# Receiver.net
KiCad netlist of a schematic drawn in Altium Designer
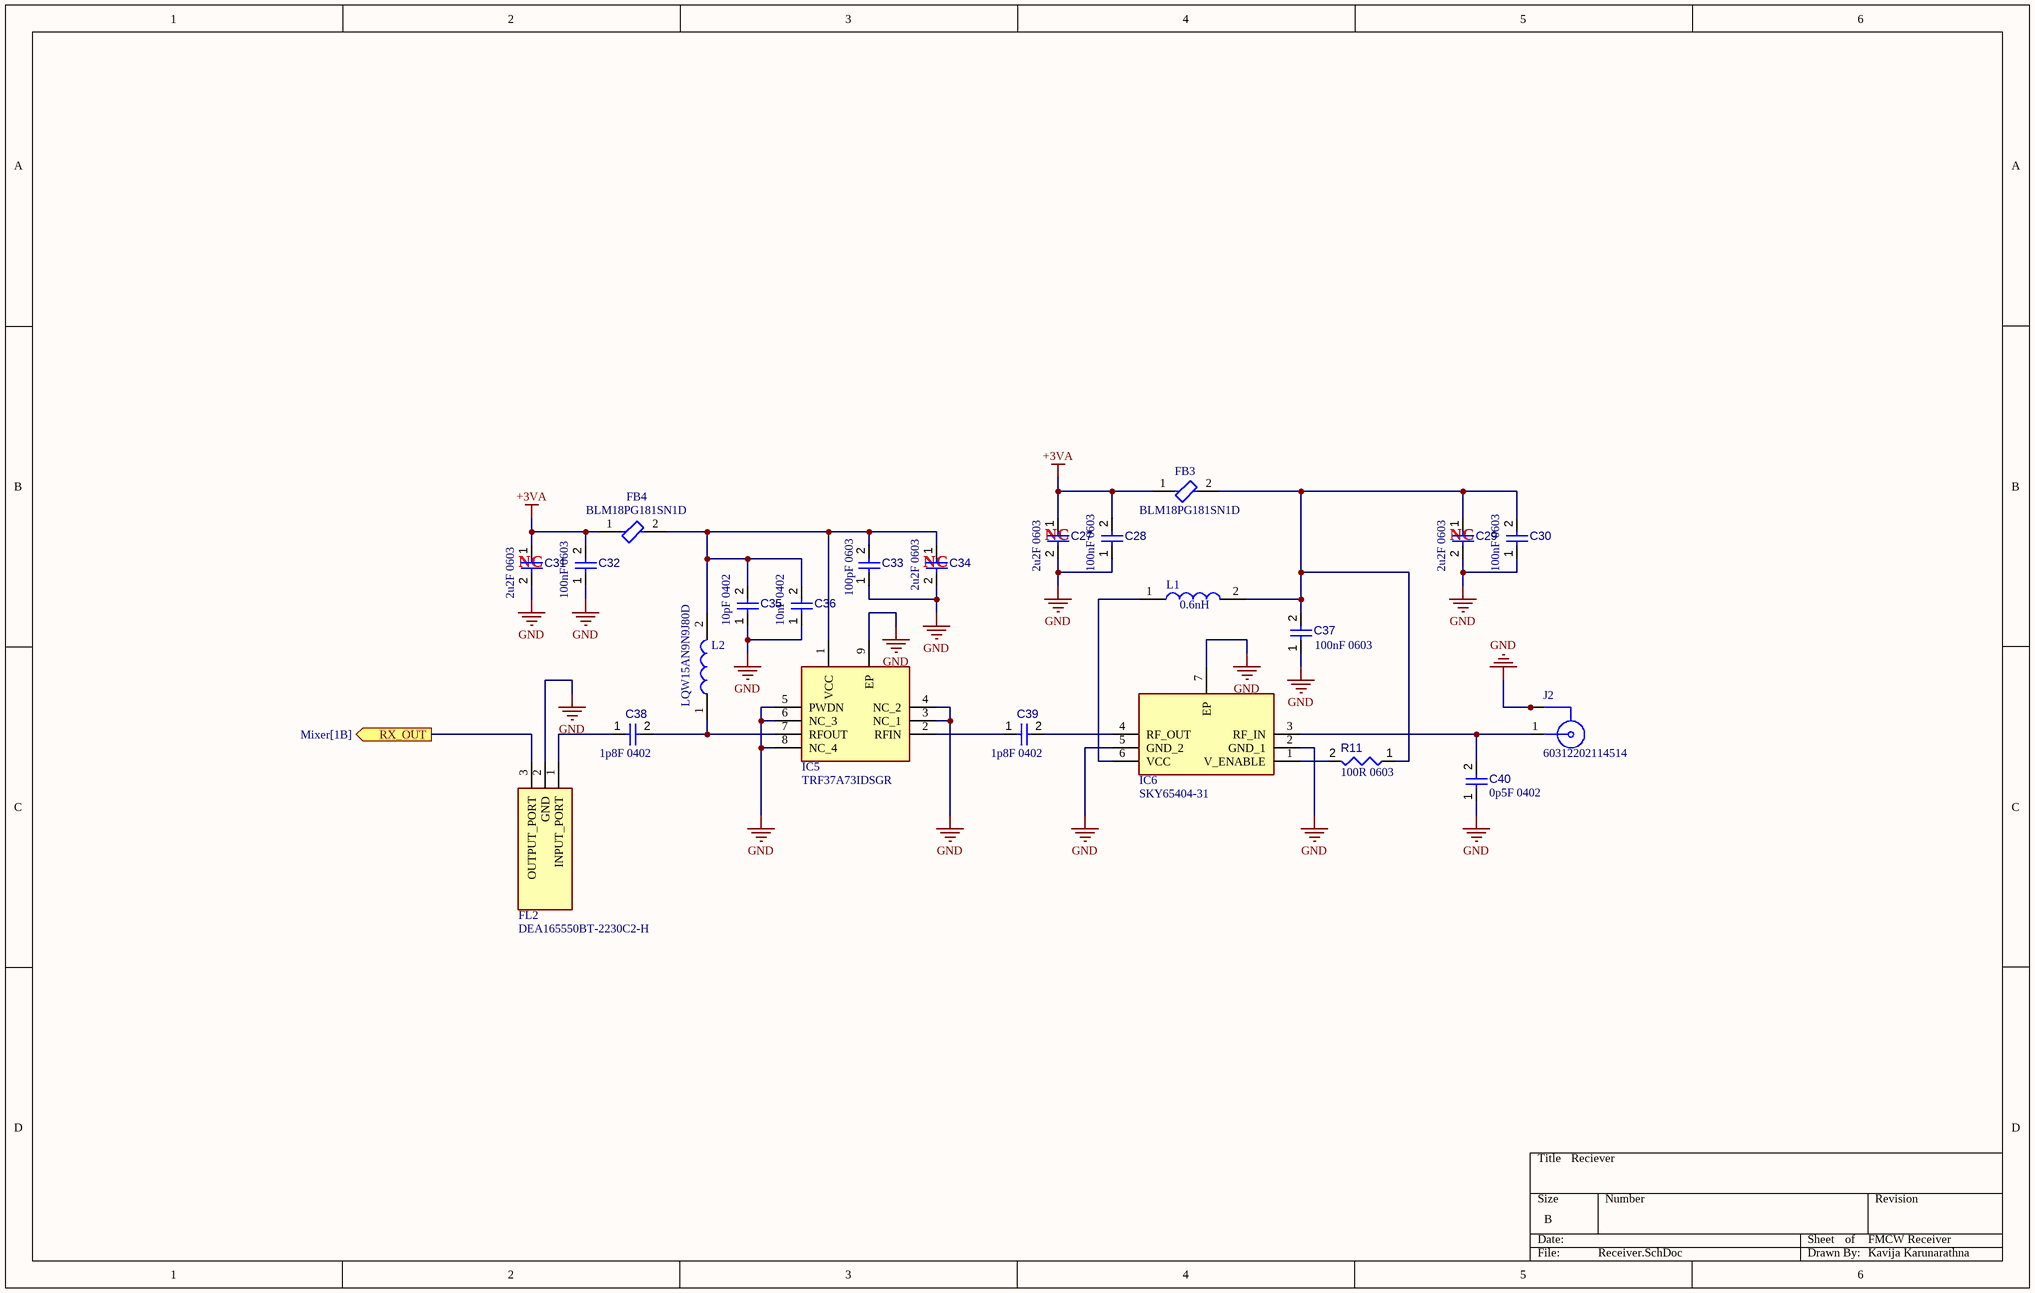
[diagram p0: Receiver.SchDoc]

(export (version "E")
  (design (tool "Eeschema 10.0.6"))
  (components
    (comp (ref "C27")
      (value "2u2F 0603")
      (footprint "CAPC0603(1608)100_L")
      (description "Multilayer Ceramic Capacitors MLCC - SMD/SMT 0603 10nF 16volts X7R 10%")
      (fields (field (name "TOLERANCE") "20%") (field (name "MANUFACTURER PART NO") "VJ0603G225KXQCW1BC"))
      (libsource (lib "Kavija Karunarathna") (part "CAP-NP-2"))
    )
    (comp (ref "C28")
      (value "100nF 0603")
      (footprint "CAPC0603(1608)100_L")
      (description "Chip Capacitor, 1µF +/-0.1%, 25V, 0603, Thickness 1 mm")
      (fields (field (name "TOLERANCE") "20%") (field (name "MANUFACTURER PART NO") "0603X104K250CT"))
      (libsource (lib "Kavija Karunarathna") (part "CAP-NP-2"))
    )
    (comp (ref "C29")
      (value "2u2F 0603")
      (footprint "CAPC0603(1608)100_L")
      (description "Multilayer Ceramic Capacitors MLCC - SMD/SMT 0603 10nF 16volts X7R 10%")
      (fields (field (name "TOLERANCE") "20%") (field (name "MANUFACTURER PART NO") "VJ0603G225KXQCW1BC"))
      (libsource (lib "Kavija Karunarathna") (part "CAP-NP-2"))
    )
    (comp (ref "C30")
      (value "100nF 0603")
      (footprint "CAPC0603(1608)100_L")
      (description "Chip Capacitor, 1µF +/-0.1%, 25V, 0603, Thickness 1 mm")
      (fields (field (name "TOLERANCE") "20%") (field (name "MANUFACTURER PART NO") "0603X104K250CT"))
      (libsource (lib "Kavija Karunarathna") (part "CAP-NP-2"))
    )
    (comp (ref "C31")
      (value "2u2F 0603")
      (footprint "CAPC0603(1608)100_L")
      (description "Multilayer Ceramic Capacitors MLCC - SMD/SMT 0603 10nF 16volts X7R 10%")
      (fields (field (name "TOLERANCE") "20%") (field (name "MANUFACTURER PART NO") "VJ0603G225KXQCW1BC"))
      (libsource (lib "Kavija Karunarathna") (part "CAP-NP-2"))
    )
    (comp (ref "C32")
      (value "100nF 0603")
      (footprint "CAPC0603(1608)100_L")
      (description "Chip Capacitor, 1µF +/-0.1%, 25V, 0603, Thickness 1 mm")
      (fields (field (name "TOLERANCE") "20%") (field (name "MANUFACTURER PART NO") "0603X104K250CT"))
      (libsource (lib "Kavija Karunarathna") (part "CAP-NP-2"))
    )
    (comp (ref "C33")
      (value "100pF 0603")
      (footprint "CAPC0603(1608)100_L")
      (description "Chip Capacitor, 1µF +/-0.1%, 25V, 0603, Thickness 1 mm")
      (fields (field (name "TOLERANCE") "20%") (field (name "MANUFACTURER PART NO") "06033A101GAT2A"))
      (libsource (lib "Kavija Karunarathna") (part "CAP-NP-2"))
    )
    (comp (ref "C34")
      (value "2u2F 0603")
      (footprint "CAPC0603(1608)100_L")
      (description "Multilayer Ceramic Capacitors MLCC - SMD/SMT 0603 10nF 16volts X7R 10%")
      (fields (field (name "TOLERANCE") "20%") (field (name "MANUFACTURER PART NO") "VJ0603G225KXQCW1BC"))
      (libsource (lib "Kavija Karunarathna") (part "CAP-NP-2"))
    )
    (comp (ref "C35")
      (value "10pF 0402")
      (footprint "CAPC0402(1005)60_L")
      (description "Multilayer Ceramic Capacitors MLCC - SMD/SMT 50 V 10 pF C0G 0402 1%")
      (fields (field (name "TOLERANCE") "20%") (field (name "MANUFACTURER PART NO") "CQ0402FRNPO9BN100"))
      (libsource (lib "Kavija Karunarathna") (part "CAP-NP-2"))
    )
    (comp (ref "C36")
      (value "10nF 0402")
      (footprint "CAPC0402(1005)60_L")
      (description "Multilayer Ceramic Capacitors MLCC - SMD/SMT 50 V 10 pF C0G 0402 1%")
      (fields (field (name "TOLERANCE") "20%") (field (name "MANUFACTURER PART NO") "VJ0402Y103JXJAC"))
      (libsource (lib "Kavija Karunarathna") (part "CAP-NP-2"))
    )
    (comp (ref "C37")
      (value "100nF 0603")
      (footprint "CAPC0603(1608)100_L")
      (description "Chip Capacitor, 1µF +/-0.1%, 25V, 0603, Thickness 1 mm")
      (fields (field (name "TOLERANCE") "20%") (field (name "MANUFACTURER PART NO") "0603X104K250CT"))
      (libsource (lib "Kavija Karunarathna") (part "CAP-NP-2"))
    )
    (comp (ref "C38")
      (value "1p8F 0402")
      (footprint "CAPC0402(1005)60_L")
      (description "Multilayer Ceramic Capacitors MLCC - SMD/SMT 50 V 10 pF C0G 0402 1%")
      (fields (field (name "TOLERANCE") "20%") (field (name "MANUFACTURER PART NO") "GJM1555C1H1R8CB01J"))
      (libsource (lib "Kavija Karunarathna") (part "CAP-NP-2"))
    )
    (comp (ref "C39")
      (value "1p8F 0402")
      (footprint "CAPC0402(1005)60_L")
      (description "Multilayer Ceramic Capacitors MLCC - SMD/SMT 50 V 10 pF C0G 0402 1%")
      (fields (field (name "TOLERANCE") "20%") (field (name "MANUFACTURER PART NO") "GJM1555C1H1R8CB01J"))
      (libsource (lib "Kavija Karunarathna") (part "CAP-NP-2"))
    )
    (comp (ref "C40")
      (value "0p5F 0402")
      (footprint "CAPC0402(1005)60_L")
      (description "Multilayer Ceramic Capacitors MLCC - SMD/SMT 50 V 10 pF C0G 0402 1%")
      (fields (field (name "TOLERANCE") "20%") (field (name "MANUFACTURER PART NO") "04025A0R5BAT4A"))
      (libsource (lib "Kavija Karunarathna") (part "CAP-NP-2"))
    )
    (comp (ref "FB3")
      (value "BLM18PG181SN1D")
      (footprint "FB-0603")
      (description "FERRITE BEAD 0603")
      (fields (field (name "MOUSER PART NO") "81-BLM18PG181SN1D"))
      (libsource (lib "SchLib") (part "742792662-FB"))
    )
    (comp (ref "FB4")
      (value "BLM18PG181SN1D")
      (footprint "FB-0603")
      (description "FERRITE BEAD 0603")
      (fields (field (name "MOUSER PART NO") "81-BLM18PG181SN1D"))
      (libsource (lib "SchLib") (part "742792662-FB"))
    )
    (comp (ref "FL2")
      (value "DEA165550BT-2230C2-H")
      (footprint "DEA165550BT-2230C2-H")
      (description "Filter")
      (fields
        (field (name "ARROW PART NUMBER") "DEA165550BT-2322A1-H")
        (field (name "MOUSER PART NO") "810-DEA16555BT223C2H")
      )
      (libsource (lib "SchLib") (part "DEA165550BT-2230C2-H"))
    )
    (comp (ref "IC5")
      (value "TRF37A73IDSGR")
      (footprint "SON50P200X200X80-9N")
      (description "Integrated Circuit")
      (fields (field (name "MOUSER PART NO") "595-TRF37A73IDSGR"))
      (libsource (lib "SchLib") (part "TRF37A73IDSGR"))
    )
    (comp (ref "IC6")
      (value "SKY65404-31")
      (footprint "SON50P150X150X50-7N-D")
      (description "Integrated Circuit")
      (fields (field (name "MOUSER PART NO") "873-SKY65404-31"))
      (libsource (lib "SchLib") (part "SKY65404-31"))
    )
    (comp (ref "J2")
      (value "60312202114514")
      (footprint "60312202114514")
      (fields
        (field (name "MF") "{'manufacturer': u'~{W}xfcrth Elektronik'}")
        (field (name "MOUSER PART NO") "710-60312202114514")
      )
      (libsource (lib "Kavija Karunarathna") (part "60312202114514"))
    )
    (comp (ref "L1")
      (value "0.6nH")
      (footprint "LQP03HQ0N5B02D")
      (description "Inductor")
      (fields
        (field (name "MANUFACTURER PART NO") "LQP03HQ0N6C02D")
        (field (name "MOUSER PART NO") "81-LQP03HQ0N6C02D")
      )
      (libsource (lib "SchLib") (part "LQP03HQ0N6C02D"))
    )
    (comp (ref "L2")
      (value "LQW15AN9N9J80D")
      (footprint "LQW15AN10NG80D")
      (description "Inductor")
      (fields (field (name "MOUSER PART NO") "81-LQW15AN9N9J80D"))
      (libsource (lib "SchLib") (part "LQW15AN9N9J80D"))
    )
    (comp (ref "R11")
      (value "100R 0603")
      (footprint "RESC0603(1608)_L")
      (description "Thick Film Resistors - SMD WRIS-RSKS 100 Ohms 1 % 0.1 W 0603 AEC-Q200")
      (fields (field (name "POWER") "100mW") (field (name "TOLERANCE") "5%"))
      (libsource (lib "Kavija Karunarathna") (part "120R3J"))
    )
  )
  (nets
    (net (code "1") (name "+3VA") (class "Default")
      (node (ref "C27") (pin "1") (pinfunction "1_1") (pintype "passive"))
      (node (ref "C28") (pin "2") (pinfunction "2_2") (pintype "passive"))
      (node (ref "C31") (pin "1") (pinfunction "1_1") (pintype "passive"))
      (node (ref "C32") (pin "2") (pinfunction "2_2") (pintype "passive"))
      (node (ref "FB3") (pin "1") (pinfunction "1_1") (pintype "passive"))
      (node (ref "FB4") (pin "1") (pinfunction "1_1") (pintype "passive"))
    )
    (net (code "2") (name "/RX_OUT") (class "Default")
      (node (ref "FL2") (pin "3") (pinfunction "OUTPUT_PORT_3") (pintype "passive"))
    )
    (net (code "3") (name "GND") (class "Default")
      (node (ref "C27") (pin "2") (pinfunction "2_2") (pintype "passive"))
      (node (ref "C28") (pin "1") (pinfunction "1_1") (pintype "passive"))
      (node (ref "C29") (pin "2") (pinfunction "2_2") (pintype "passive"))
      (node (ref "C30") (pin "1") (pinfunction "1_1") (pintype "passive"))
      (node (ref "C31") (pin "2") (pinfunction "2_2") (pintype "passive"))
      (node (ref "C32") (pin "1") (pinfunction "1_1") (pintype "passive"))
      (node (ref "C33") (pin "1") (pinfunction "1_1") (pintype "passive"))
      (node (ref "C34") (pin "2") (pinfunction "2_2") (pintype "passive"))
      (node (ref "C35") (pin "1") (pinfunction "1_1") (pintype "passive"))
      (node (ref "C36") (pin "1") (pinfunction "1_1") (pintype "passive"))
      (node (ref "C37") (pin "1") (pinfunction "1_1") (pintype "passive"))
      (node (ref "C40") (pin "1") (pinfunction "1_1") (pintype "passive"))
      (node (ref "FL2") (pin "2") (pinfunction "GND_2") (pintype "passive"))
      (node (ref "IC5") (pin "3") (pinfunction "NC_1_3") (pintype "passive"))
      (node (ref "IC5") (pin "4") (pinfunction "NC_2_4") (pintype "passive"))
      (node (ref "IC5") (pin "5") (pinfunction "PWDN_5") (pintype "passive"))
      (node (ref "IC5") (pin "6") (pinfunction "NC_3_6") (pintype "passive"))
      (node (ref "IC5") (pin "8") (pinfunction "NC_4_8") (pintype "passive"))
      (node (ref "IC5") (pin "9") (pinfunction "EP_9") (pintype "passive"))
      (node (ref "IC6") (pin "2") (pinfunction "GND_1_2") (pintype "passive"))
      (node (ref "IC6") (pin "5") (pinfunction "GND_2_5") (pintype "passive"))
      (node (ref "IC6") (pin "7") (pinfunction "EP_7") (pintype "passive"))
      (node (ref "J2") (pin "2") (pinfunction "2_2") (pintype "passive"))
      (node (ref "J2") (pin "3") (pinfunction "2_3") (pintype "passive"))
      (node (ref "J2") (pin "4") (pinfunction "2_4") (pintype "passive"))
      (node (ref "J2") (pin "5") (pinfunction "2_5") (pintype "passive"))
    )
    (net (code "4") (name "Net-(C29-Pad1)") (class "Default")
      (node (ref "C29") (pin "1") (pinfunction "1_1") (pintype "passive"))
      (node (ref "C30") (pin "2") (pinfunction "2_2") (pintype "passive"))
      (node (ref "C37") (pin "2") (pinfunction "2_2") (pintype "passive"))
      (node (ref "FB3") (pin "2") (pinfunction "2_2") (pintype "passive"))
      (node (ref "L1") (pin "2") (pinfunction "2_2") (pintype "passive"))
      (node (ref "R11") (pin "1") (pinfunction "1_1") (pintype "passive"))
    )
    (net (code "5") (name "Net-(FL2-INPUT_PORT)") (class "Default")
      (node (ref "C38") (pin "1") (pinfunction "1_1") (pintype "passive"))
      (node (ref "FL2") (pin "1") (pinfunction "INPUT_PORT_1") (pintype "passive"))
    )
    (net (code "6") (name "Net-(IC5-RFIN)") (class "Default")
      (node (ref "C39") (pin "1") (pinfunction "1_1") (pintype "passive"))
      (node (ref "IC5") (pin "2") (pinfunction "RFIN_2") (pintype "passive"))
    )
    (net (code "7") (name "Net-(IC5-RFOUT)") (class "Default")
      (node (ref "C38") (pin "2") (pinfunction "2_2") (pintype "passive"))
      (node (ref "IC5") (pin "7") (pinfunction "RFOUT_7") (pintype "passive"))
      (node (ref "L2") (pin "1") (pinfunction "1_1") (pintype "passive"))
    )
    (net (code "8") (name "Net-(IC5-VCC)") (class "Default")
      (node (ref "C33") (pin "2") (pinfunction "2_2") (pintype "passive"))
      (node (ref "C34") (pin "1") (pinfunction "1_1") (pintype "passive"))
      (node (ref "C35") (pin "2") (pinfunction "2_2") (pintype "passive"))
      (node (ref "C36") (pin "2") (pinfunction "2_2") (pintype "passive"))
      (node (ref "FB4") (pin "2") (pinfunction "2_2") (pintype "passive"))
      (node (ref "IC5") (pin "1") (pinfunction "VCC_1") (pintype "passive"))
      (node (ref "L2") (pin "2") (pinfunction "2_2") (pintype "passive"))
    )
    (net (code "9") (name "Net-(IC6-RF_IN)") (class "Default")
      (node (ref "C40") (pin "2") (pinfunction "2_2") (pintype "passive"))
      (node (ref "IC6") (pin "3") (pinfunction "RF_IN_3") (pintype "passive"))
      (node (ref "J2") (pin "1") (pinfunction "1_1") (pintype "passive"))
    )
    (net (code "10") (name "Net-(IC6-RF_OUT)") (class "Default")
      (node (ref "C39") (pin "2") (pinfunction "2_2") (pintype "passive"))
      (node (ref "IC6") (pin "4") (pinfunction "RF_OUT_4") (pintype "passive"))
    )
    (net (code "11") (name "Net-(IC6-VCC)") (class "Default")
      (node (ref "IC6") (pin "6") (pinfunction "VCC_6") (pintype "passive"))
      (node (ref "L1") (pin "1") (pinfunction "1_1") (pintype "passive"))
    )
    (net (code "12") (name "Net-(IC6-V_ENABLE)") (class "Default")
      (node (ref "IC6") (pin "1") (pinfunction "V_ENABLE_1") (pintype "passive"))
      (node (ref "R11") (pin "2") (pinfunction "2_2") (pintype "passive"))
    )
  )
)
